# DAC_ADC.net
KiCad netlist of a schematic drawn in Altium Designer
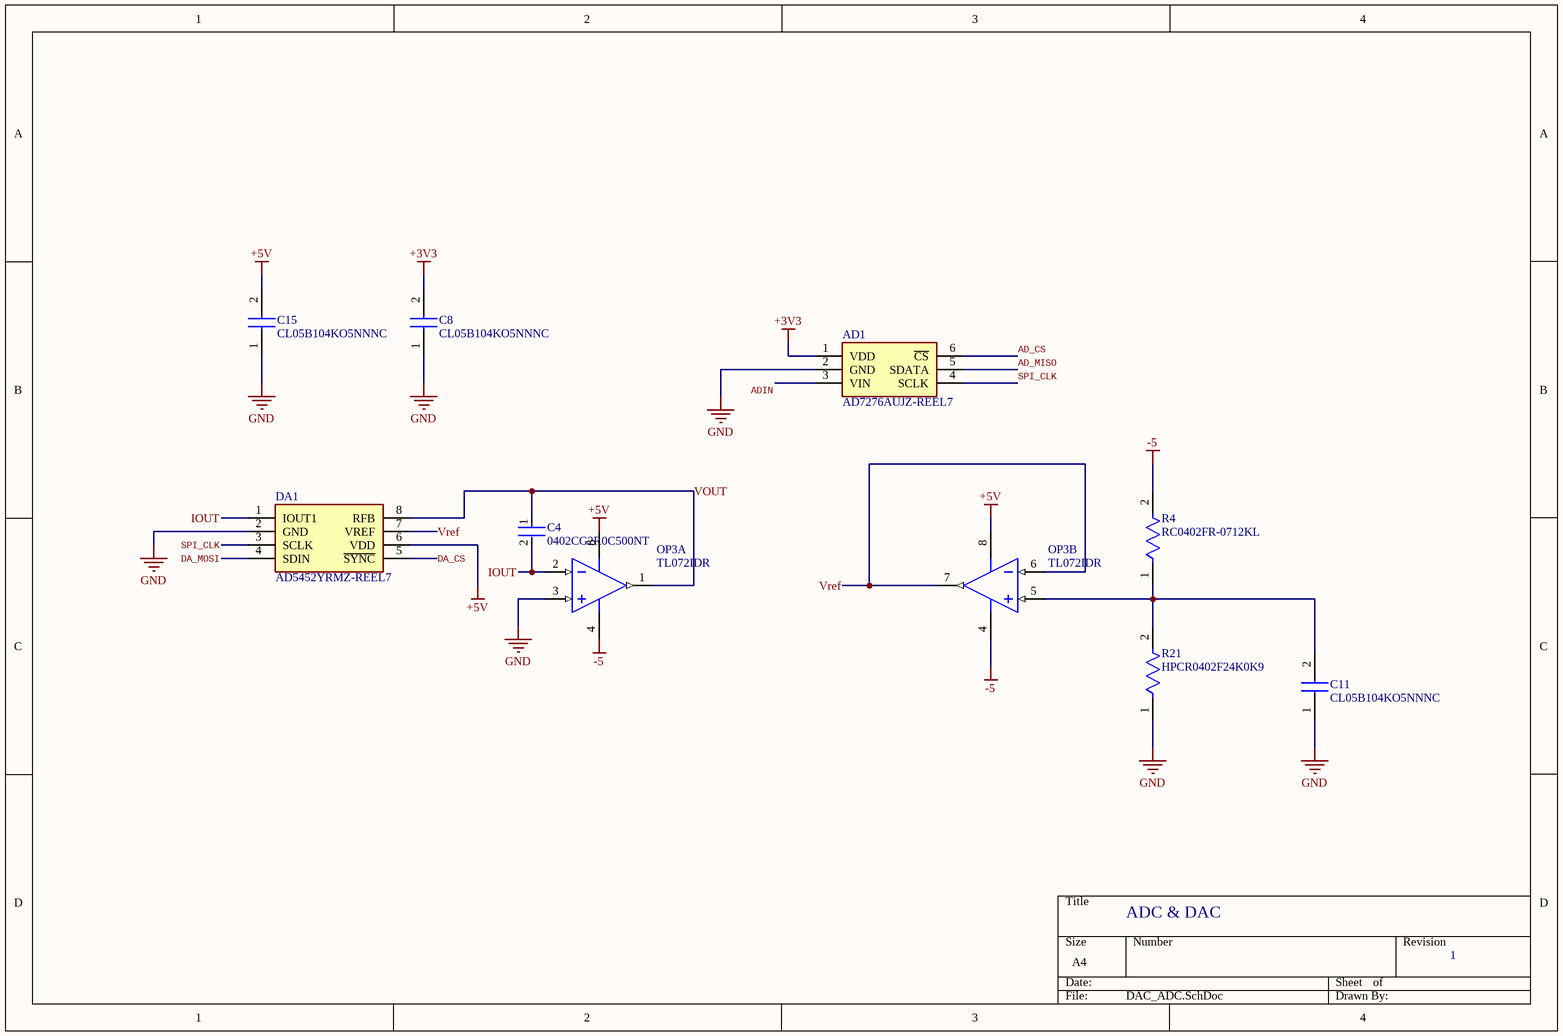
[diagram p0: DAC_ADC.SchDoc]

(export (version "E")
  (design (tool "Eeschema 10.0.6"))
  (components
    (comp (ref "AD1")
      (value "AD7276AUJZ-REEL7")
      (footprint "SamacSys:SOT95P280X100-6N")
      (description "Integrated Circuit")
      (fields (field (name "MOUSER PART NUMBER") "584-AD7276AUJZ-R7"))
      (libsource (lib "*") (part "AD7276AUJZ-REEL7"))
    )
    (comp (ref "C4")
      (value "0402CG2R0C500NT")
      (footprint "FP-GJM155-0_05-IPC_C")
      (description "Multi-Layer Ceramic Capacitor 2pF C0G  ±0.1pF 0402 Paper T/R")
      (libsource (lib "Altium Content Vault") (part "02cd4be3c70576c341d710602a673aa"))
    )
    (comp (ref "C8")
      (value "CL05B104KO5NNNC")
      (footprint "SamacSys:CAPC1005X55N")
      (description "Capacitor")
      (fields (field (name "MOUSER PART NUMBER") "187-CL05B104KO5NNNC"))
      (libsource (lib "*") (part "CL05B104KO5NNNC"))
    )
    (comp (ref "C11")
      (value "CL05B104KO5NNNC")
      (footprint "SamacSys:CAPC1005X55N")
      (description "Capacitor")
      (fields (field (name "MOUSER PART NUMBER") "187-CL05B104KO5NNNC"))
      (libsource (lib "*") (part "CL05B104KO5NNNC"))
    )
    (comp (ref "C15")
      (value "CL05B104KO5NNNC")
      (footprint "SamacSys:CAPC1005X55N")
      (description "Capacitor")
      (fields (field (name "MOUSER PART NUMBER") "187-CL05B104KO5NNNC"))
      (libsource (lib "*") (part "CL05B104KO5NNNC"))
    )
    (comp (ref "DA1")
      (value "AD5452YRMZ-REEL7")
      (footprint "SamacSys:SOP65P490X110-8N")
      (description "Integrated Circuit")
      (fields (field (name "MOUSER PART NUMBER") "584-AD5452YRMZ-R7"))
      (libsource (lib "*") (part "AD5452YRMZ-REEL7"))
    )
    (comp (ref "OP3")
      (value "TL072IDR")
      (footprint "D0008A_L")
      (fields (field (name "MANUFACTURER") "Texas Instruments"))
      (libsource (lib "Altium Content Vault") (part "TI-AMP-D6-2-8_D"))
    )
    (comp (ref "R4")
      (value "RC0402FR-0712KL")
      (footprint "FP-RC0402-0_4-IPC_C")
      (description "RES SMD 12K OHM 1% 1/16W 0402")
      (fields (field (name "TOLERANCE") "1%"))
      (libsource (lib "Altium Content Vault") (part "1029c3af85768c4190bb7ad29bc67b5"))
    )
    (comp (ref "R21")
      (value "HPCR0402F24K0K9")
      (footprint "FP-RT0402-MFG")
      (description "RES SMD 12K OHM 1% 1/16W 0402")
      (fields
        (field (name "TOLERANCE") "0.01")
        (field (name "OCTOPART") "https://octopart.com/rt0402fre0714kl-yageo-1378200")
      )
      (libsource (lib "Altium Content Vault") (part "1029c3af85768c4190bb7ad29bc67b5"))
    )
  )
  (nets
    (net (code "1") (name "+3V3") (class "Default")
      (node (ref "AD1") (pin "1") (pinfunction "VDD_1") (pintype "passive"))
      (node (ref "C8") (pin "2") (pinfunction "2_2") (pintype "passive"))
    )
    (net (code "2") (name "+5V") (class "Default")
      (node (ref "C15") (pin "2") (pinfunction "2_2") (pintype "passive"))
      (node (ref "DA1") (pin "6") (pinfunction "VDD_6") (pintype "passive"))
      (node (ref "OP3") (pin "8") (pinfunction "VCC+_8") (pintype "power_in"))
    )
    (net (code "3") (name "-5") (class "Default")
      (node (ref "OP3") (pin "4") (pinfunction "VCC-_4") (pintype "passive"))
      (node (ref "R4") (pin "2") (pinfunction "2_2") (pintype "passive"))
    )
    (net (code "4") (name "/ADIN") (class "Default")
      (node (ref "AD1") (pin "3") (pinfunction "VIN_3") (pintype "passive"))
    )
    (net (code "5") (name "/AD_CS") (class "Default")
      (node (ref "AD1") (pin "6") (pinfunction "~{CS}_6") (pintype "passive"))
    )
    (net (code "6") (name "/AD_MISO") (class "Default")
      (node (ref "AD1") (pin "5") (pinfunction "SDATA_5") (pintype "passive"))
    )
    (net (code "7") (name "/DA_CS") (class "Default")
      (node (ref "DA1") (pin "5") (pinfunction "~{SYNC}_5") (pintype "passive"))
    )
    (net (code "8") (name "/DA_MOSI") (class "Default")
      (node (ref "DA1") (pin "4") (pinfunction "SDIN_4") (pintype "passive"))
    )
    (net (code "9") (name "/IOUT") (class "Default")
      (node (ref "C4") (pin "2") (pinfunction "2_2") (pintype "passive"))
      (node (ref "DA1") (pin "1") (pinfunction "IOUT1_1") (pintype "passive"))
      (node (ref "OP3") (pin "2") (pinfunction "IN1-_2") (pintype "input"))
    )
    (net (code "10") (name "/SPI_CLK") (class "Default")
      (node (ref "AD1") (pin "4") (pinfunction "SCLK_4") (pintype "passive"))
      (node (ref "DA1") (pin "3") (pinfunction "SCLK_3") (pintype "passive"))
    )
    (net (code "11") (name "/VOUT") (class "Default")
      (node (ref "C4") (pin "1") (pinfunction "1_1") (pintype "passive"))
      (node (ref "DA1") (pin "8") (pinfunction "RFB_8") (pintype "passive"))
      (node (ref "OP3") (pin "1") (pinfunction "OUT1_1") (pintype "output"))
    )
    (net (code "12") (name "/Vref") (class "Default")
      (node (ref "DA1") (pin "7") (pinfunction "VREF_7") (pintype "passive"))
      (node (ref "OP3") (pin "6") (pinfunction "IN2-_6") (pintype "input"))
      (node (ref "OP3") (pin "7") (pinfunction "OUT2_7") (pintype "output"))
    )
    (net (code "13") (name "GND") (class "Default")
      (node (ref "AD1") (pin "2") (pinfunction "GND_2") (pintype "passive"))
      (node (ref "C11") (pin "1") (pinfunction "1_1") (pintype "passive"))
      (node (ref "C15") (pin "1") (pinfunction "1_1") (pintype "passive"))
      (node (ref "C8") (pin "1") (pinfunction "1_1") (pintype "passive"))
      (node (ref "DA1") (pin "2") (pinfunction "GND_2") (pintype "passive"))
      (node (ref "OP3") (pin "3") (pinfunction "IN1+_3") (pintype "input"))
      (node (ref "R21") (pin "1") (pinfunction "1_1") (pintype "passive"))
    )
    (net (code "14") (name "Net-(OP3B-IN2+)") (class "Default")
      (node (ref "C11") (pin "2") (pinfunction "2_2") (pintype "passive"))
      (node (ref "OP3") (pin "5") (pinfunction "IN2+_5") (pintype "input"))
      (node (ref "R21") (pin "2") (pinfunction "2_2") (pintype "passive"))
      (node (ref "R4") (pin "1") (pinfunction "1_1") (pintype "passive"))
    )
  )
)
